# design.net
KiCad netlist of a schematic drawn in Altium Designer
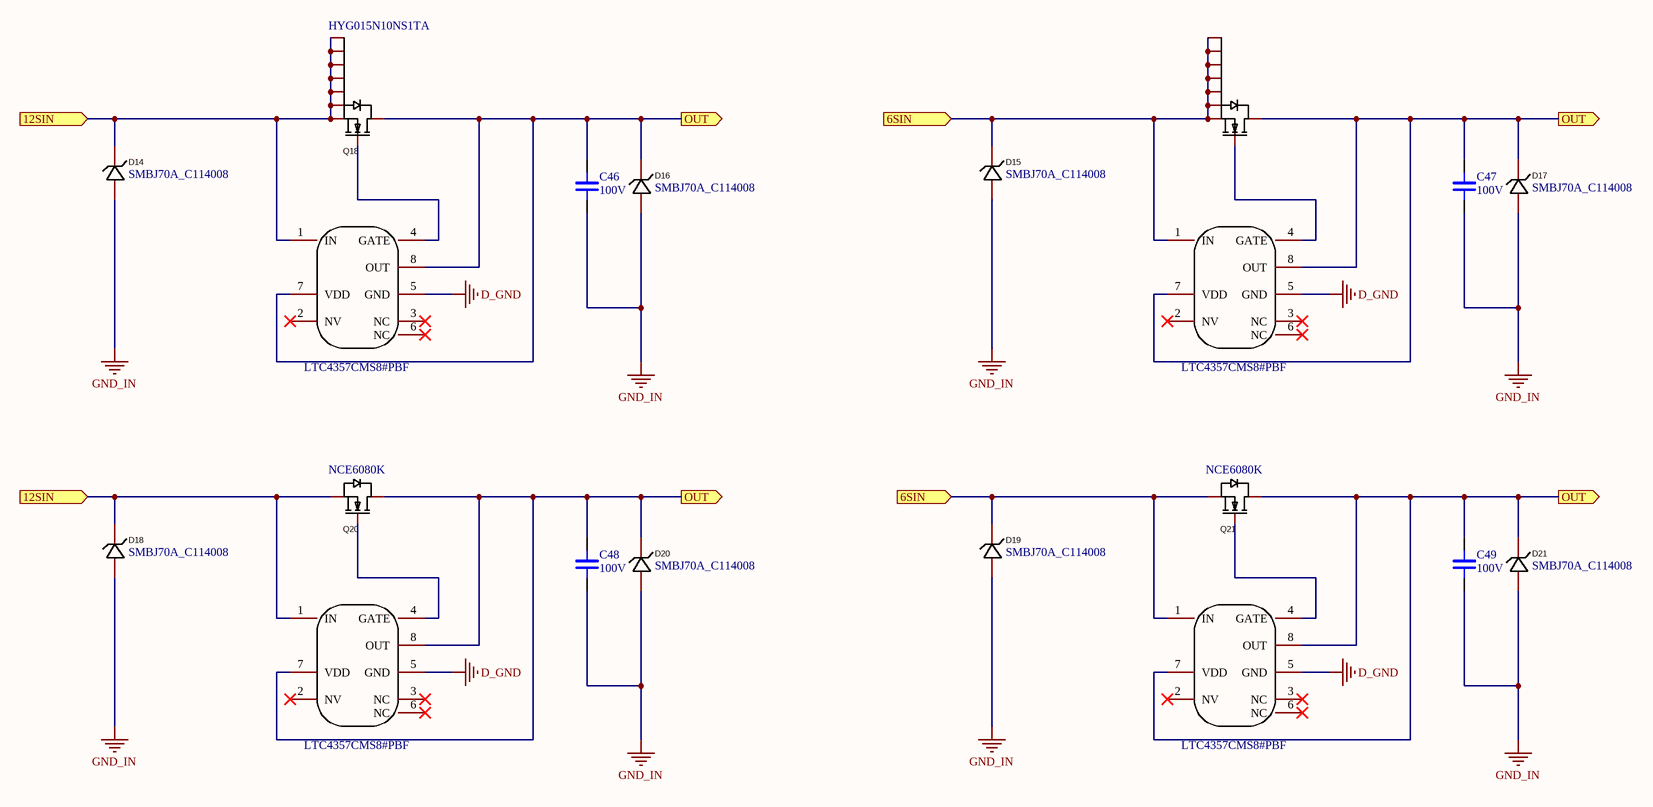
[diagram p0: 理想二极管.SchDoc]

(export (version "E")
  (design (tool "Eeschema 10.0.6"))
  (components
    (comp (ref "C46")
      (value "100V")
      (footprint "C 1210_L")
      (description "陶瓷电容")
      (libsource (lib "HERO_通用") (part "CAP"))
    )
    (comp (ref "C47")
      (value "100V")
      (footprint "C 1210_L")
      (description "陶瓷电容")
      (libsource (lib "HERO_通用") (part "CAP"))
    )
    (comp (ref "C48")
      (value "100V")
      (footprint "C 1210_L")
      (description "陶瓷电容")
      (libsource (lib "HERO_通用") (part "CAP"))
    )
    (comp (ref "C49")
      (value "100V")
      (footprint "C 1210_L")
      (description "陶瓷电容")
      (libsource (lib "HERO_通用") (part "CAP"))
    )
    (comp (ref "D14")
      (value "SMBJ70A_C114008")
      (footprint "SMB_L4.6-W3.6-LS5.3-RD")
      (fields (field (name "MANUFACTURER") "MDD") (field (name "MANUFACTURER PART") "SMBJ70A"))
      (libsource (lib "Schlib1") (part "SMBJ70A_C114008"))
    )
    (comp (ref "D15")
      (value "SMBJ70A_C114008")
      (footprint "SMB_L4.6-W3.6-LS5.3-RD")
      (fields (field (name "MANUFACTURER") "MDD") (field (name "MANUFACTURER PART") "SMBJ70A"))
      (libsource (lib "Schlib1") (part "SMBJ70A_C114008"))
    )
    (comp (ref "D16")
      (value "SMBJ70A_C114008")
      (footprint "SMB_L4.6-W3.6-LS5.3-RD")
      (fields (field (name "MANUFACTURER") "MDD") (field (name "MANUFACTURER PART") "SMBJ70A"))
      (libsource (lib "Schlib1") (part "SMBJ70A_C114008"))
    )
    (comp (ref "D17")
      (value "SMBJ70A_C114008")
      (footprint "SMB_L4.6-W3.6-LS5.3-RD")
      (fields (field (name "MANUFACTURER") "MDD") (field (name "MANUFACTURER PART") "SMBJ70A"))
      (libsource (lib "Schlib1") (part "SMBJ70A_C114008"))
    )
    (comp (ref "D18")
      (value "SMBJ70A_C114008")
      (footprint "SMB_L4.6-W3.6-LS5.3-RD")
      (fields (field (name "MANUFACTURER") "MDD") (field (name "MANUFACTURER PART") "SMBJ70A"))
      (libsource (lib "Schlib1") (part "SMBJ70A_C114008"))
    )
    (comp (ref "D19")
      (value "SMBJ70A_C114008")
      (footprint "SMB_L4.6-W3.6-LS5.3-RD")
      (fields (field (name "MANUFACTURER") "MDD") (field (name "MANUFACTURER PART") "SMBJ70A"))
      (libsource (lib "Schlib1") (part "SMBJ70A_C114008"))
    )
    (comp (ref "D20")
      (value "SMBJ70A_C114008")
      (footprint "SMB_L4.6-W3.6-LS5.3-RD")
      (fields (field (name "MANUFACTURER") "MDD") (field (name "MANUFACTURER PART") "SMBJ70A"))
      (libsource (lib "Schlib1") (part "SMBJ70A_C114008"))
    )
    (comp (ref "D21")
      (value "SMBJ70A_C114008")
      (footprint "SMB_L4.6-W3.6-LS5.3-RD")
      (fields (field (name "MANUFACTURER") "MDD") (field (name "MANUFACTURER PART") "SMBJ70A"))
      (libsource (lib "Schlib1") (part "SMBJ70A_C114008"))
    )
    (comp (ref "Q18")
      (value "HYG015N10NS1TA")
      (footprint "TOLL-8_L10.4-W9.9-P1.20-LS11.7-BL")
      (fields (field (name "MANUFACTURER") "HUAYI(华羿微)"))
      (libsource (lib "Schlib1") (part "HYG015N10NS1TA"))
    )
    (comp (ref "Q19")
      (value "HYG015N10NS1TA")
      (footprint "TOLL-8_L10.4-W9.9-P1.20-LS11.7-BL")
      (fields (field (name "MANUFACTURER") "HUAYI(华羿微)"))
      (libsource (lib "Schlib1") (part "HYG015N10NS1TA"))
    )
    (comp (ref "Q20")
      (value "NCE6080K")
      (footprint "TO-252-2_L6.6-W6.1-P4.57-LS10.1-BR-CW")
      (fields (field (name "MANUFACTURER") "NCE(无锡新洁能)"))
      (libsource (lib "Schlib1") (part "NCE6080K"))
    )
    (comp (ref "Q21")
      (value "NCE6080K")
      (footprint "TO-252-2_L6.6-W6.1-P4.57-LS10.1-BR-CW")
      (fields (field (name "MANUFACTURER") "NCE(无锡新洁能)"))
      (libsource (lib "Schlib1") (part "NCE6080K"))
    )
    (comp (ref "U10")
      (value "LTC4357CMS8#PBF")
      (footprint "MSOP-8_L3.0-W3.0-P0.65-LS4.9-BL")
      (fields (field (name "MANUFACTURER") "ADI(亚德诺)/LINEAR(凌特)"))
      (libsource (lib "Schlib1") (part "LTC4357CMS8#PBF"))
    )
    (comp (ref "U11")
      (value "LTC4357CMS8#PBF")
      (footprint "MSOP-8_L3.0-W3.0-P0.65-LS4.9-BL")
      (fields (field (name "MANUFACTURER") "ADI(亚德诺)/LINEAR(凌特)"))
      (libsource (lib "Schlib1") (part "LTC4357CMS8#PBF"))
    )
    (comp (ref "U12")
      (value "LTC4357CMS8#PBF")
      (footprint "MSOP-8_L3.0-W3.0-P0.65-LS4.9-BL")
      (fields (field (name "MANUFACTURER") "ADI(亚德诺)/LINEAR(凌特)"))
      (libsource (lib "Schlib1") (part "LTC4357CMS8#PBF"))
    )
    (comp (ref "U13")
      (value "LTC4357CMS8#PBF")
      (footprint "MSOP-8_L3.0-W3.0-P0.65-LS4.9-BL")
      (fields (field (name "MANUFACTURER") "ADI(亚德诺)/LINEAR(凌特)"))
      (libsource (lib "Schlib1") (part "LTC4357CMS8#PBF"))
    )
  )
  (nets
    (net (code "1") (name "/6SIN") (class "Default")
      (node (ref "D15") (pin "1") (pinfunction "C_1") (pintype "passive"))
      (node (ref "D19") (pin "1") (pinfunction "C_1") (pintype "passive"))
      (node (ref "Q19") (pin "2") (pinfunction "S_2") (pintype "passive"))
      (node (ref "Q19") (pin "3") (pinfunction "S_3") (pintype "passive"))
      (node (ref "Q19") (pin "4") (pinfunction "S_4") (pintype "passive"))
      (node (ref "Q19") (pin "5") (pinfunction "S_5") (pintype "passive"))
      (node (ref "Q19") (pin "6") (pinfunction "S_6") (pintype "passive"))
      (node (ref "Q19") (pin "7") (pinfunction "S_7") (pintype "passive"))
      (node (ref "Q19") (pin "8") (pinfunction "S_8") (pintype "passive"))
      (node (ref "Q21") (pin "3") (pinfunction "S_3") (pintype "passive"))
      (node (ref "U11") (pin "1") (pinfunction "IN_1") (pintype "passive"))
      (node (ref "U13") (pin "1") (pinfunction "IN_1") (pintype "passive"))
    )
    (net (code "2") (name "/12SIN") (class "Default")
      (node (ref "D14") (pin "1") (pinfunction "C_1") (pintype "passive"))
      (node (ref "D18") (pin "1") (pinfunction "C_1") (pintype "passive"))
      (node (ref "Q18") (pin "2") (pinfunction "S_2") (pintype "passive"))
      (node (ref "Q18") (pin "3") (pinfunction "S_3") (pintype "passive"))
      (node (ref "Q18") (pin "4") (pinfunction "S_4") (pintype "passive"))
      (node (ref "Q18") (pin "5") (pinfunction "S_5") (pintype "passive"))
      (node (ref "Q18") (pin "6") (pinfunction "S_6") (pintype "passive"))
      (node (ref "Q18") (pin "7") (pinfunction "S_7") (pintype "passive"))
      (node (ref "Q18") (pin "8") (pinfunction "S_8") (pintype "passive"))
      (node (ref "Q20") (pin "3") (pinfunction "S_3") (pintype "passive"))
      (node (ref "U10") (pin "1") (pinfunction "IN_1") (pintype "passive"))
      (node (ref "U12") (pin "1") (pinfunction "IN_1") (pintype "passive"))
    )
    (net (code "3") (name "/OUT") (class "Default")
      (node (ref "C46") (pin "1") (pinfunction "1_1") (pintype "passive"))
      (node (ref "C47") (pin "1") (pinfunction "1_1") (pintype "passive"))
      (node (ref "C48") (pin "1") (pinfunction "1_1") (pintype "passive"))
      (node (ref "C49") (pin "1") (pinfunction "1_1") (pintype "passive"))
      (node (ref "D16") (pin "1") (pinfunction "C_1") (pintype "passive"))
      (node (ref "D17") (pin "1") (pinfunction "C_1") (pintype "passive"))
      (node (ref "D20") (pin "1") (pinfunction "C_1") (pintype "passive"))
      (node (ref "D21") (pin "1") (pinfunction "C_1") (pintype "passive"))
      (node (ref "Q18") (pin "9") (pinfunction "D_9") (pintype "passive"))
      (node (ref "Q19") (pin "9") (pinfunction "D_9") (pintype "passive"))
      (node (ref "Q20") (pin "2") (pinfunction "D_2") (pintype "passive"))
      (node (ref "Q21") (pin "2") (pinfunction "D_2") (pintype "passive"))
      (node (ref "U10") (pin "7") (pinfunction "VDD_7") (pintype "passive"))
      (node (ref "U10") (pin "8") (pinfunction "OUT_8") (pintype "passive"))
      (node (ref "U11") (pin "7") (pinfunction "VDD_7") (pintype "passive"))
      (node (ref "U11") (pin "8") (pinfunction "OUT_8") (pintype "passive"))
      (node (ref "U12") (pin "7") (pinfunction "VDD_7") (pintype "passive"))
      (node (ref "U12") (pin "8") (pinfunction "OUT_8") (pintype "passive"))
      (node (ref "U13") (pin "7") (pinfunction "VDD_7") (pintype "passive"))
      (node (ref "U13") (pin "8") (pinfunction "OUT_8") (pintype "passive"))
    )
    (net (code "4") (name "D_GND") (class "Default")
      (node (ref "U10") (pin "5") (pinfunction "GND_5") (pintype "passive"))
      (node (ref "U11") (pin "5") (pinfunction "GND_5") (pintype "passive"))
      (node (ref "U12") (pin "5") (pinfunction "GND_5") (pintype "passive"))
      (node (ref "U13") (pin "5") (pinfunction "GND_5") (pintype "passive"))
    )
    (net (code "5") (name "GND_IN") (class "Default")
      (node (ref "C46") (pin "2") (pinfunction "2_2") (pintype "passive"))
      (node (ref "C47") (pin "2") (pinfunction "2_2") (pintype "passive"))
      (node (ref "C48") (pin "2") (pinfunction "2_2") (pintype "passive"))
      (node (ref "C49") (pin "2") (pinfunction "2_2") (pintype "passive"))
      (node (ref "D14") (pin "2") (pinfunction "A_2") (pintype "passive"))
      (node (ref "D15") (pin "2") (pinfunction "A_2") (pintype "passive"))
      (node (ref "D16") (pin "2") (pinfunction "A_2") (pintype "passive"))
      (node (ref "D17") (pin "2") (pinfunction "A_2") (pintype "passive"))
      (node (ref "D18") (pin "2") (pinfunction "A_2") (pintype "passive"))
      (node (ref "D19") (pin "2") (pinfunction "A_2") (pintype "passive"))
      (node (ref "D20") (pin "2") (pinfunction "A_2") (pintype "passive"))
      (node (ref "D21") (pin "2") (pinfunction "A_2") (pintype "passive"))
    )
    (net (code "6") (name "Net-(Q18-G)") (class "Default")
      (node (ref "Q18") (pin "1") (pinfunction "G_1") (pintype "passive"))
      (node (ref "U10") (pin "4") (pinfunction "GATE_4") (pintype "passive"))
    )
    (net (code "7") (name "Net-(Q19-G)") (class "Default")
      (node (ref "Q19") (pin "1") (pinfunction "G_1") (pintype "passive"))
      (node (ref "U11") (pin "4") (pinfunction "GATE_4") (pintype "passive"))
    )
    (net (code "8") (name "Net-(Q20-G)") (class "Default")
      (node (ref "Q20") (pin "1") (pinfunction "G_1") (pintype "passive"))
      (node (ref "U12") (pin "4") (pinfunction "GATE_4") (pintype "passive"))
    )
    (net (code "9") (name "Net-(Q21-G)") (class "Default")
      (node (ref "Q21") (pin "1") (pinfunction "G_1") (pintype "passive"))
      (node (ref "U13") (pin "4") (pinfunction "GATE_4") (pintype "passive"))
    )
    (net (code "10") (name "unconnected-(U10-NC-Pad3)") (class "Default")
      (node (ref "U10") (pin "3") (pinfunction "NC_3") (pintype "passive+no_connect"))
    )
    (net (code "11") (name "unconnected-(U10-NC-Pad6)") (class "Default")
      (node (ref "U10") (pin "6") (pinfunction "NC_6") (pintype "passive+no_connect"))
    )
    (net (code "12") (name "unconnected-(U10-NV-Pad2)") (class "Default")
      (node (ref "U10") (pin "2") (pinfunction "NV_2") (pintype "passive+no_connect"))
    )
    (net (code "13") (name "unconnected-(U11-NC-Pad3)") (class "Default")
      (node (ref "U11") (pin "3") (pinfunction "NC_3") (pintype "passive+no_connect"))
    )
    (net (code "14") (name "unconnected-(U11-NC-Pad6)") (class "Default")
      (node (ref "U11") (pin "6") (pinfunction "NC_6") (pintype "passive+no_connect"))
    )
    (net (code "15") (name "unconnected-(U11-NV-Pad2)") (class "Default")
      (node (ref "U11") (pin "2") (pinfunction "NV_2") (pintype "passive+no_connect"))
    )
    (net (code "16") (name "unconnected-(U12-NC-Pad3)") (class "Default")
      (node (ref "U12") (pin "3") (pinfunction "NC_3") (pintype "passive+no_connect"))
    )
    (net (code "17") (name "unconnected-(U12-NC-Pad6)") (class "Default")
      (node (ref "U12") (pin "6") (pinfunction "NC_6") (pintype "passive+no_connect"))
    )
    (net (code "18") (name "unconnected-(U12-NV-Pad2)") (class "Default")
      (node (ref "U12") (pin "2") (pinfunction "NV_2") (pintype "passive+no_connect"))
    )
    (net (code "19") (name "unconnected-(U13-NC-Pad3)") (class "Default")
      (node (ref "U13") (pin "3") (pinfunction "NC_3") (pintype "passive+no_connect"))
    )
    (net (code "20") (name "unconnected-(U13-NC-Pad6)") (class "Default")
      (node (ref "U13") (pin "6") (pinfunction "NC_6") (pintype "passive+no_connect"))
    )
    (net (code "21") (name "unconnected-(U13-NV-Pad2)") (class "Default")
      (node (ref "U13") (pin "2") (pinfunction "NV_2") (pintype "passive+no_connect"))
    )
  )
)
